# c200_rev_b.net
KiCad netlist of a schematic drawn in EAGLE
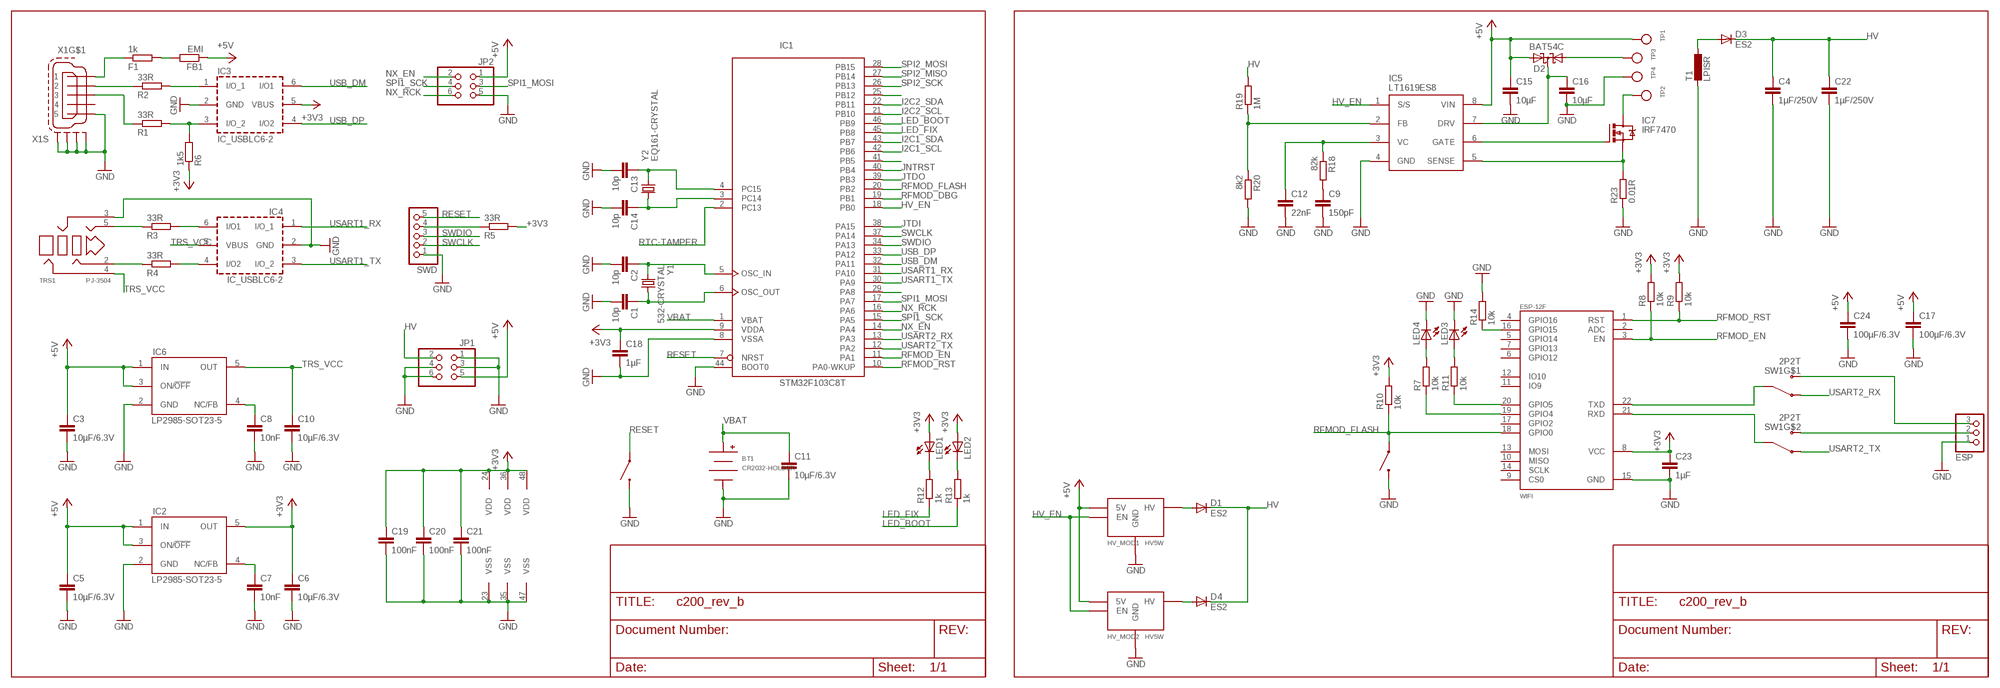
[diagram p0: schematic, sheet 1]

(export (version "E")
  (design (tool "Eeschema 10.0.6"))
  (components
    (comp (ref "BT1")
      (value "CR2032-HOLDER")
      (footprint "eagle-import:CH28-2032LF")
      (libsource (lib "eagle-import") (part "CR2032-HOLDER"))
    )
    (comp (ref "C1")
      (value "10p")
      (footprint "eagle-import:C0603")
      (libsource (lib "eagle-import") (part "C-EUC0603"))
    )
    (comp (ref "C2")
      (value "10p")
      (footprint "eagle-import:C0603")
      (libsource (lib "eagle-import") (part "C-EUC0603"))
    )
    (comp (ref "C3")
      (value "10µF/6.3V")
      (footprint "eagle-import:C0603")
      (libsource (lib "eagle-import") (part "C-EUC0603"))
    )
    (comp (ref "C4")
      (value "1µF/250V")
      (footprint "eagle-import:C2220K")
      (libsource (lib "eagle-import") (part "C-EUC2220K"))
    )
    (comp (ref "C5")
      (value "10µF/6.3V")
      (footprint "eagle-import:C0603")
      (libsource (lib "eagle-import") (part "C-EUC0603"))
    )
    (comp (ref "C6")
      (value "10µF/6.3V")
      (footprint "eagle-import:C0603")
      (libsource (lib "eagle-import") (part "C-EUC0603"))
    )
    (comp (ref "C7")
      (value "10nF")
      (footprint "eagle-import:C0603")
      (libsource (lib "eagle-import") (part "C-EUC0603"))
    )
    (comp (ref "C8")
      (value "10nF")
      (footprint "eagle-import:C0603")
      (libsource (lib "eagle-import") (part "C-EUC0603"))
    )
    (comp (ref "C9")
      (value "150pF")
      (footprint "eagle-import:C0603")
      (libsource (lib "eagle-import") (part "C-EUC0603"))
    )
    (comp (ref "C10")
      (value "10µF/6.3V")
      (footprint "eagle-import:C0603")
      (libsource (lib "eagle-import") (part "C-EUC0603"))
    )
    (comp (ref "C11")
      (value "10µF/6.3V")
      (footprint "eagle-import:C0603")
      (libsource (lib "eagle-import") (part "C-EUC0603"))
    )
    (comp (ref "C12")
      (value "22nF")
      (footprint "eagle-import:C0603")
      (libsource (lib "eagle-import") (part "C-EUC0603"))
    )
    (comp (ref "C13")
      (value "10p")
      (footprint "eagle-import:C0603")
      (libsource (lib "eagle-import") (part "C-EUC0603"))
    )
    (comp (ref "C14")
      (value "10p")
      (footprint "eagle-import:C0603")
      (libsource (lib "eagle-import") (part "C-EUC0603"))
    )
    (comp (ref "C15")
      (value "10µF")
      (footprint "eagle-import:C0603")
      (libsource (lib "eagle-import") (part "C-EUC0603"))
    )
    (comp (ref "C16")
      (value "10µF")
      (footprint "eagle-import:C0603")
      (libsource (lib "eagle-import") (part "C-EUC0603"))
    )
    (comp (ref "C17")
      (value "100µF/6.3V")
      (footprint "eagle-import:C1210")
      (libsource (lib "eagle-import") (part "C-EUC1210"))
    )
    (comp (ref "C18")
      (value "1µF")
      (footprint "eagle-import:C0603")
      (libsource (lib "eagle-import") (part "C-EUC0603"))
    )
    (comp (ref "C19")
      (value "100nF")
      (footprint "eagle-import:C0603")
      (libsource (lib "eagle-import") (part "C-EUC0603"))
    )
    (comp (ref "C20")
      (value "100nF")
      (footprint "eagle-import:C0603")
      (libsource (lib "eagle-import") (part "C-EUC0603"))
    )
    (comp (ref "C21")
      (value "100nF")
      (footprint "eagle-import:C0603")
      (libsource (lib "eagle-import") (part "C-EUC0603"))
    )
    (comp (ref "C22")
      (value "1µF/250V")
      (footprint "eagle-import:C2220K")
      (libsource (lib "eagle-import") (part "C-EUC2220K"))
    )
    (comp (ref "C23")
      (value "1µF")
      (footprint "eagle-import:C0603")
      (libsource (lib "eagle-import") (part "C-EUC0603"))
    )
    (comp (ref "C24")
      (value "100µF/6.3V")
      (footprint "eagle-import:C1210")
      (libsource (lib "eagle-import") (part "C-EUC1210"))
    )
    (comp (ref "D1")
      (value "ES2")
      (footprint "eagle-import:DO-214AA")
      (libsource (lib "eagle-import") (part "ES2"))
    )
    (comp (ref "D2")
      (value "BAT54C")
      (footprint "eagle-import:SOT23")
      (libsource (lib "eagle-import") (part "BAT54C"))
    )
    (comp (ref "D3")
      (value "ES2")
      (footprint "eagle-import:DO-214AA")
      (libsource (lib "eagle-import") (part "ES2"))
    )
    (comp (ref "D4")
      (value "ES2")
      (footprint "eagle-import:DO-214AA")
      (libsource (lib "eagle-import") (part "ES2"))
    )
    (comp (ref "ESP")
      (value "HEADER-1X3ROUND")
      (footprint "eagle-import:1X03_ROUND")
      (libsource (lib "eagle-import") (part "HEADER-1X3ROUND"))
    )
    (comp (ref "F1")
      (value "1k")
      (footprint "eagle-import:R0603")
      (libsource (lib "eagle-import") (part "R-EU_R0603"))
    )
    (comp (ref "FB1")
      (value "EMI")
      (footprint "eagle-import:R0603")
      (libsource (lib "eagle-import") (part "R-EU_R0603"))
    )
    (comp (ref "FLASH")
      (value "TACT-SWITCH-40-40")
      (footprint "eagle-import:40-40")
      (libsource (lib "eagle-import") (part "TACT-SWITCH-40-40"))
    )
    (comp (ref "HV_MOD1")
      (value "HV5W")
      (footprint "eagle-import:HV5W-D")
      (libsource (lib "eagle-import") (part "HV5W"))
    )
    (comp (ref "HV_MOD2")
      (value "HV5W")
      (footprint "eagle-import:HV5W-D")
      (libsource (lib "eagle-import") (part "HV5W"))
    )
    (comp (ref "IC1")
      (value "STM32F103C8T")
      (footprint "eagle-import:LQFP48")
      (libsource (lib "eagle-import") (part "STM32F103CT8"))
    )
    (comp (ref "IC2")
      (value "LP2985-SOT23-5")
      (footprint "eagle-import:SOT23-5")
      (libsource (lib "eagle-import") (part "LP2985-SOT23-5"))
    )
    (comp (ref "IC3")
      (value "IC_USBLC6-2")
      (footprint "eagle-import:SOT-23-6L")
      (libsource (lib "eagle-import") (part "IC_USBLC6-2"))
    )
    (comp (ref "IC4")
      (value "IC_USBLC6-2")
      (footprint "eagle-import:SOT-23-6L")
      (libsource (lib "eagle-import") (part "IC_USBLC6-2"))
    )
    (comp (ref "IC5")
      (value "LT1619ES8")
      (footprint "eagle-import:SO8")
      (libsource (lib "eagle-import") (part "LT1619ES8"))
    )
    (comp (ref "IC6")
      (value "LP2985-SOT23-5")
      (footprint "eagle-import:SOT23-5")
      (libsource (lib "eagle-import") (part "LP2985-SOT23-5"))
    )
    (comp (ref "IC7")
      (value "IRF7470")
      (footprint "eagle-import:SO8")
      (libsource (lib "eagle-import") (part "IRF7470"))
    )
    (comp (ref "ISP")
      (value "TACT-SWITCH-40-40")
      (footprint "eagle-import:40-40")
      (libsource (lib "eagle-import") (part "TACT-SWITCH-40-40"))
    )
    (comp (ref "JP1")
      (value "PINHD-2X3_2.54-SMD")
      (footprint "eagle-import:2X03SMD")
      (libsource (lib "eagle-import") (part "PINHD-2X3_2.54-SMD"))
    )
    (comp (ref "JP2")
      (value "PINHD-2X3_2.54-SMD")
      (footprint "eagle-import:2X03SMD")
      (libsource (lib "eagle-import") (part "PINHD-2X3_2.54-SMD"))
    )
    (comp (ref "LED1")
      (value "LEDCHIP-LED0603")
      (footprint "eagle-import:CHIP-LED0603")
      (libsource (lib "eagle-import") (part "LEDCHIP-LED0603"))
    )
    (comp (ref "LED2")
      (value "LEDCHIP-LED0603")
      (footprint "eagle-import:CHIP-LED0603")
      (libsource (lib "eagle-import") (part "LEDCHIP-LED0603"))
    )
    (comp (ref "LED3")
      (value "LEDCHIP-LED0603")
      (footprint "eagle-import:CHIP-LED0603")
      (libsource (lib "eagle-import") (part "LEDCHIP-LED0603"))
    )
    (comp (ref "LED4")
      (value "LEDCHIP-LED0603")
      (footprint "eagle-import:CHIP-LED0603")
      (libsource (lib "eagle-import") (part "LEDCHIP-LED0603"))
    )
    (comp (ref "R1")
      (value "33R")
      (footprint "eagle-import:R0603")
      (libsource (lib "eagle-import") (part "R-EU_R0603"))
    )
    (comp (ref "R2")
      (value "33R")
      (footprint "eagle-import:R0603")
      (libsource (lib "eagle-import") (part "R-EU_R0603"))
    )
    (comp (ref "R3")
      (value "33R")
      (footprint "eagle-import:R0603")
      (libsource (lib "eagle-import") (part "R-EU_R0603"))
    )
    (comp (ref "R4")
      (value "33R")
      (footprint "eagle-import:R0603")
      (libsource (lib "eagle-import") (part "R-EU_R0603"))
    )
    (comp (ref "R5")
      (value "33R")
      (footprint "eagle-import:R0603")
      (libsource (lib "eagle-import") (part "R-EU_R0603"))
    )
    (comp (ref "R6")
      (value "1k5")
      (footprint "eagle-import:R0603")
      (libsource (lib "eagle-import") (part "R-EU_R0603"))
    )
    (comp (ref "R7")
      (value "10k")
      (footprint "eagle-import:R0603")
      (libsource (lib "eagle-import") (part "R-EU_R0603"))
    )
    (comp (ref "R8")
      (value "10k")
      (footprint "eagle-import:R0603")
      (libsource (lib "eagle-import") (part "R-EU_R0603"))
    )
    (comp (ref "R9")
      (value "10k")
      (footprint "eagle-import:R0603")
      (libsource (lib "eagle-import") (part "R-EU_R0603"))
    )
    (comp (ref "R10")
      (value "10k")
      (footprint "eagle-import:R0603")
      (libsource (lib "eagle-import") (part "R-EU_R0603"))
    )
    (comp (ref "R11")
      (value "10k")
      (footprint "eagle-import:R0603")
      (libsource (lib "eagle-import") (part "R-EU_R0603"))
    )
    (comp (ref "R12")
      (value "1k")
      (footprint "eagle-import:R0603")
      (libsource (lib "eagle-import") (part "R-EU_R0603"))
    )
    (comp (ref "R13")
      (value "1k")
      (footprint "eagle-import:R0603")
      (libsource (lib "eagle-import") (part "R-EU_R0603"))
    )
    (comp (ref "R14")
      (value "10k")
      (footprint "eagle-import:R0603")
      (libsource (lib "eagle-import") (part "R-EU_R0603"))
    )
    (comp (ref "R18")
      (value "82k")
      (footprint "eagle-import:R0603")
      (libsource (lib "eagle-import") (part "R-EU_R0603"))
    )
    (comp (ref "R19")
      (value "1M")
      (footprint "eagle-import:M1206")
      (libsource (lib "eagle-import") (part "R-EU_M1206"))
    )
    (comp (ref "R20")
      (value "8k2")
      (footprint "eagle-import:R0603")
      (libsource (lib "eagle-import") (part "R-EU_R0603"))
    )
    (comp (ref "R23")
      (value "0.01R")
      (footprint "eagle-import:R1206")
      (libsource (lib "eagle-import") (part "R-EU_R1206"))
    )
    (comp (ref "SW1")
      (value "2P2T")
      (footprint "eagle-import:MSS22D18")
      (libsource (lib "eagle-import") (part "2P2T"))
    )
    (comp (ref "SWD")
      (value "HEADER-1X5ROUND")
      (footprint "eagle-import:1X05_ROUND")
      (libsource (lib "eagle-import") (part "HEADER-1X5ROUND"))
    )
    (comp (ref "T1")
      (value "LPISR")
      (footprint "eagle-import:PISR")
      (libsource (lib "eagle-import") (part "LPISR"))
    )
    (comp (ref "TP1")
      (value "TESTPOINTROUND2MM")
      (footprint "eagle-import:TESTPOINT_ROUND_2MM")
      (libsource (lib "eagle-import") (part "TESTPOINTROUND2MM"))
    )
    (comp (ref "TP2")
      (value "TESTPOINTROUND2MM")
      (footprint "eagle-import:TESTPOINT_ROUND_2MM")
      (libsource (lib "eagle-import") (part "TESTPOINTROUND2MM"))
    )
    (comp (ref "TP3")
      (value "TESTPOINTROUND2MM")
      (footprint "eagle-import:TESTPOINT_ROUND_2MM")
      (libsource (lib "eagle-import") (part "TESTPOINTROUND2MM"))
    )
    (comp (ref "TP4")
      (value "TESTPOINTROUND2MM")
      (footprint "eagle-import:TESTPOINT_ROUND_2MM")
      (libsource (lib "eagle-import") (part "TESTPOINTROUND2MM"))
    )
    (comp (ref "TRS1")
      (value "PJ-3504")
      (footprint "eagle-import:YD-PJ-3504")
      (libsource (lib "eagle-import") (part "PJ-3504"))
    )
    (comp (ref "WIFI")
      (value "ESP-12F")
      (footprint "eagle-import:ESP-12F")
      (libsource (lib "eagle-import") (part "ESP-12F"))
    )
    (comp (ref "X1")
      (value "MINI-USB-SCHIELD-32005-201")
      (footprint "eagle-import:32005-201")
      (libsource (lib "eagle-import") (part "MINI-USB-SCHIELD-32005-201"))
    )
    (comp (ref "Y1")
      (value "532-CRYSTAL")
      (footprint "eagle-import:2PIN50X32")
      (libsource (lib "eagle-import") (part "532-CRYSTAL"))
    )
    (comp (ref "Y2")
      (value "EQ161-CRYSTAL")
      (footprint "eagle-import:EQ161")
      (libsource (lib "eagle-import") (part "EQ161-CRYSTAL"))
    )
  )
  (nets
    (net (code "1") (name "+3V3") (class "Default")
      (node (ref "C18") (pin "1") (pinfunction "1_1") (pintype "passive"))
      (node (ref "C19") (pin "1") (pinfunction "1_1") (pintype "passive"))
      (node (ref "C20") (pin "1") (pinfunction "1_1") (pintype "passive"))
      (node (ref "C21") (pin "1") (pinfunction "1_1") (pintype "passive"))
      (node (ref "C23") (pin "1") (pinfunction "1_1") (pintype "passive"))
      (node (ref "C6") (pin "1") (pinfunction "1_1") (pintype "passive"))
      (node (ref "IC1") (pin "24") (pinfunction "VDD_24") (pintype "power_in"))
      (node (ref "IC1") (pin "36") (pinfunction "VDD_36") (pintype "power_in"))
      (node (ref "IC1") (pin "48") (pinfunction "VDD_48") (pintype "power_in"))
      (node (ref "IC1") (pin "9") (pinfunction "VDDA_9") (pintype "power_in"))
      (node (ref "IC2") (pin "5") (pinfunction "OUT_5") (pintype "bidirectional"))
      (node (ref "IC3") (pin "5") (pinfunction "VBUS_5") (pintype "bidirectional"))
      (node (ref "LED1") (pin "A") (pinfunction "A_A") (pintype "passive"))
      (node (ref "LED2") (pin "A") (pinfunction "A_A") (pintype "passive"))
      (node (ref "R10") (pin "2") (pinfunction "2_2") (pintype "passive"))
      (node (ref "R5") (pin "2") (pinfunction "2_2") (pintype "passive"))
      (node (ref "R6") (pin "1") (pinfunction "1_1") (pintype "passive"))
      (node (ref "R8") (pin "2") (pinfunction "2_2") (pintype "passive"))
      (node (ref "R9") (pin "2") (pinfunction "2_2") (pintype "passive"))
      (node (ref "WIFI") (pin "8") (pinfunction "VCC_8") (pintype "bidirectional"))
    )
    (net (code "2") (name "+5V") (class "Default")
      (node (ref "C15") (pin "1") (pinfunction "1_1") (pintype "passive"))
      (node (ref "C17") (pin "1") (pinfunction "1_1") (pintype "passive"))
      (node (ref "C24") (pin "1") (pinfunction "1_1") (pintype "passive"))
      (node (ref "C3") (pin "1") (pinfunction "1_1") (pintype "passive"))
      (node (ref "C5") (pin "1") (pinfunction "1_1") (pintype "passive"))
      (node (ref "D2") (pin "2") (pinfunction "A2_2") (pintype "passive"))
      (node (ref "FB1") (pin "1") (pinfunction "1_1") (pintype "passive"))
      (node (ref "HV_MOD1") (pin "+5V") (pinfunction "5V_+5V") (pintype "bidirectional"))
      (node (ref "HV_MOD2") (pin "+5V") (pinfunction "5V_+5V") (pintype "bidirectional"))
      (node (ref "IC2") (pin "1") (pinfunction "IN_1") (pintype "bidirectional"))
      (node (ref "IC2") (pin "3") (pinfunction "ON/~{OFF}_3") (pintype "bidirectional"))
      (node (ref "IC5") (pin "8") (pinfunction "VIN_8") (pintype "bidirectional"))
      (node (ref "IC6") (pin "1") (pinfunction "IN_1") (pintype "bidirectional"))
      (node (ref "IC6") (pin "3") (pinfunction "ON/~{OFF}_3") (pintype "bidirectional"))
      (node (ref "JP1") (pin "5") (pinfunction "5_5") (pintype "passive"))
      (node (ref "JP2") (pin "1") (pinfunction "1_1") (pintype "passive"))
      (node (ref "TP1") (pin "P$1") (pinfunction "P$1_P$1") (pintype "bidirectional"))
    )
    (net (code "3") (name "/HV") (class "Default")
      (node (ref "C22") (pin "1") (pinfunction "1_1") (pintype "passive"))
      (node (ref "C4") (pin "1") (pinfunction "1_1") (pintype "passive"))
      (node (ref "D1") (pin "C") (pinfunction "C_C") (pintype "passive"))
      (node (ref "D3") (pin "C") (pinfunction "C_C") (pintype "passive"))
      (node (ref "D4") (pin "C") (pinfunction "C_C") (pintype "passive"))
      (node (ref "JP1") (pin "2") (pinfunction "2_2") (pintype "passive"))
      (node (ref "R19") (pin "2") (pinfunction "2_2") (pintype "passive"))
    )
    (net (code "4") (name "/HV_EN") (class "Default")
      (node (ref "HV_MOD1") (pin "EN") (pinfunction "EN_EN") (pintype "bidirectional"))
      (node (ref "HV_MOD2") (pin "EN") (pinfunction "EN_EN") (pintype "bidirectional"))
      (node (ref "IC1") (pin "18") (pinfunction "PB0_18") (pintype "bidirectional"))
      (node (ref "IC5") (pin "1") (pinfunction "S/S_1") (pintype "bidirectional"))
    )
    (net (code "5") (name "/I2C1_SCL") (class "Default")
      (node (ref "IC1") (pin "42") (pinfunction "PB6_42") (pintype "bidirectional"))
    )
    (net (code "6") (name "/I2C1_SDA") (class "Default")
      (node (ref "IC1") (pin "43") (pinfunction "PB7_43") (pintype "bidirectional"))
    )
    (net (code "7") (name "/I2C2_SCL") (class "Default")
      (node (ref "IC1") (pin "21") (pinfunction "PB10_21") (pintype "bidirectional"))
    )
    (net (code "8") (name "/I2C2_SDA") (class "Default")
      (node (ref "IC1") (pin "22") (pinfunction "PB11_22") (pintype "bidirectional"))
    )
    (net (code "9") (name "/JNTRST") (class "Default")
      (node (ref "IC1") (pin "40") (pinfunction "PB4_40") (pintype "bidirectional"))
    )
    (net (code "10") (name "/JTDI") (class "Default")
      (node (ref "IC1") (pin "38") (pinfunction "PA15_38") (pintype "bidirectional"))
    )
    (net (code "11") (name "/JTDO") (class "Default")
      (node (ref "IC1") (pin "39") (pinfunction "PB3_39") (pintype "bidirectional"))
    )
    (net (code "12") (name "/LED_BOOT") (class "Default")
      (node (ref "IC1") (pin "46") (pinfunction "PB9_46") (pintype "bidirectional"))
      (node (ref "R13") (pin "1") (pinfunction "1_1") (pintype "passive"))
    )
    (net (code "13") (name "/LED_FIX") (class "Default")
      (node (ref "IC1") (pin "45") (pinfunction "PB8_45") (pintype "bidirectional"))
      (node (ref "R12") (pin "1") (pinfunction "1_1") (pintype "passive"))
    )
    (net (code "14") (name "/NX_EN") (class "Default")
      (node (ref "IC1") (pin "14") (pinfunction "PA4_14") (pintype "bidirectional"))
      (node (ref "JP2") (pin "2") (pinfunction "2_2") (pintype "passive"))
    )
    (net (code "15") (name "/NX_RCK") (class "Default")
      (node (ref "IC1") (pin "16") (pinfunction "PA6_16") (pintype "bidirectional"))
      (node (ref "JP2") (pin "6") (pinfunction "6_6") (pintype "passive"))
    )
    (net (code "16") (name "/RESET") (class "Default")
      (node (ref "IC1") (pin "7") (pinfunction "NRST_7") (pintype "bidirectional"))
      (node (ref "ISP") (pin "3") (pinfunction "P$2_3") (pintype "bidirectional"))
      (node (ref "ISP") (pin "4") (pinfunction "P$2_4") (pintype "bidirectional"))
      (node (ref "SWD") (pin "5") (pinfunction "5_5") (pintype "passive"))
    )
    (net (code "17") (name "/RFMOD_DBG") (class "Default")
      (node (ref "IC1") (pin "19") (pinfunction "PB1_19") (pintype "bidirectional"))
    )
    (net (code "18") (name "/RFMOD_EN") (class "Default")
      (node (ref "IC1") (pin "11") (pinfunction "PA1_11") (pintype "bidirectional"))
      (node (ref "R8") (pin "1") (pinfunction "1_1") (pintype "passive"))
      (node (ref "WIFI") (pin "3") (pinfunction "EN_3") (pintype "bidirectional"))
    )
    (net (code "19") (name "/RFMOD_FLASH") (class "Default")
      (node (ref "FLASH") (pin "3") (pinfunction "P$2_3") (pintype "bidirectional"))
      (node (ref "FLASH") (pin "4") (pinfunction "P$2_4") (pintype "bidirectional"))
      (node (ref "IC1") (pin "20") (pinfunction "PB2_20") (pintype "bidirectional"))
      (node (ref "R10") (pin "1") (pinfunction "1_1") (pintype "passive"))
      (node (ref "WIFI") (pin "18") (pinfunction "GPIO0_18") (pintype "bidirectional"))
    )
    (net (code "20") (name "/RFMOD_RST") (class "Default")
      (node (ref "IC1") (pin "10") (pinfunction "PA0-WKUP_10") (pintype "bidirectional"))
      (node (ref "R9") (pin "1") (pinfunction "1_1") (pintype "passive"))
      (node (ref "WIFI") (pin "1") (pinfunction "RST_1") (pintype "bidirectional"))
    )
    (net (code "21") (name "/RTC-TAMPER") (class "Default")
      (node (ref "IC1") (pin "2") (pinfunction "PC13_2") (pintype "bidirectional"))
    )
    (net (code "22") (name "/SPI1_MOSI") (class "Default")
      (node (ref "IC1") (pin "17") (pinfunction "PA7_17") (pintype "bidirectional"))
      (node (ref "JP2") (pin "3") (pinfunction "3_3") (pintype "passive"))
    )
    (net (code "23") (name "/SPI1_SCK") (class "Default")
      (node (ref "IC1") (pin "15") (pinfunction "PA5_15") (pintype "bidirectional"))
      (node (ref "JP2") (pin "4") (pinfunction "4_4") (pintype "passive"))
    )
    (net (code "24") (name "/SPI2_MISO") (class "Default")
      (node (ref "IC1") (pin "27") (pinfunction "PB14_27") (pintype "bidirectional"))
    )
    (net (code "25") (name "/SPI2_MOSI") (class "Default")
      (node (ref "IC1") (pin "28") (pinfunction "PB15_28") (pintype "bidirectional"))
    )
    (net (code "26") (name "/SPI2_SCK") (class "Default")
      (node (ref "IC1") (pin "26") (pinfunction "PB13_26") (pintype "bidirectional"))
    )
    (net (code "27") (name "/SWCLK") (class "Default")
      (node (ref "IC1") (pin "37") (pinfunction "PA14_37") (pintype "bidirectional"))
      (node (ref "SWD") (pin "2") (pinfunction "2_2") (pintype "passive"))
    )
    (net (code "28") (name "/SWDIO") (class "Default")
      (node (ref "IC1") (pin "34") (pinfunction "PA13_34") (pintype "bidirectional"))
      (node (ref "SWD") (pin "3") (pinfunction "3_3") (pintype "passive"))
    )
    (net (code "29") (name "/TRS_VCC") (class "Default")
      (node (ref "C10") (pin "1") (pinfunction "1_1") (pintype "passive"))
      (node (ref "IC4") (pin "5") (pinfunction "VBUS_5") (pintype "bidirectional"))
      (node (ref "IC6") (pin "5") (pinfunction "OUT_5") (pintype "bidirectional"))
      (node (ref "TRS1") (pin "4") (pinfunction "4_4") (pintype "bidirectional"))
    )
    (net (code "30") (name "/USART1_RX") (class "Default")
      (node (ref "IC1") (pin "31") (pinfunction "PA10_31") (pintype "bidirectional"))
      (node (ref "IC4") (pin "1") (pinfunction "I/O_1_1") (pintype "bidirectional"))
    )
    (net (code "31") (name "/USART1_TX") (class "Default")
      (node (ref "IC1") (pin "30") (pinfunction "PA9_30") (pintype "bidirectional"))
      (node (ref "IC4") (pin "3") (pinfunction "I/O_2_3") (pintype "bidirectional"))
    )
    (net (code "32") (name "/USART2_RX") (class "Default")
      (node (ref "IC1") (pin "13") (pinfunction "PA3_13") (pintype "bidirectional"))
      (node (ref "SW1") (pin "A1") (pinfunction "A_A1") (pintype "bidirectional"))
    )
    (net (code "33") (name "/USART2_TX") (class "Default")
      (node (ref "IC1") (pin "12") (pinfunction "PA2_12") (pintype "bidirectional"))
      (node (ref "SW1") (pin "A2") (pinfunction "A_A2") (pintype "bidirectional"))
    )
    (net (code "34") (name "/USB_DM") (class "Default")
      (node (ref "IC1") (pin "32") (pinfunction "PA11_32") (pintype "bidirectional"))
      (node (ref "IC3") (pin "6") (pinfunction "I/O1_6") (pintype "bidirectional"))
    )
    (net (code "35") (name "/USB_DP") (class "Default")
      (node (ref "IC1") (pin "33") (pinfunction "PA12_33") (pintype "bidirectional"))
      (node (ref "IC3") (pin "4") (pinfunction "I/O2_4") (pintype "bidirectional"))
    )
    (net (code "36") (name "/VBAT") (class "Default")
      (node (ref "BT1") (pin "POS") (pinfunction "POS_POS") (pintype "bidirectional"))
      (node (ref "C11") (pin "1") (pinfunction "1_1") (pintype "passive"))
      (node (ref "IC1") (pin "1") (pinfunction "VBAT_1") (pintype "power_in"))
    )
    (net (code "37") (name "GND") (class "Default")
      (node (ref "BT1") (pin "NEG") (pinfunction "NEG_NEG") (pintype "bidirectional"))
      (node (ref "C1") (pin "2") (pinfunction "2_2") (pintype "passive"))
      (node (ref "C10") (pin "2") (pinfunction "2_2") (pintype "passive"))
      (node (ref "C11") (pin "2") (pinfunction "2_2") (pintype "passive"))
      (node (ref "C12") (pin "2") (pinfunction "2_2") (pintype "passive"))
      (node (ref "C13") (pin "2") (pinfunction "2_2") (pintype "passive"))
      (node (ref "C14") (pin "2") (pinfunction "2_2") (pintype "passive"))
      (node (ref "C15") (pin "2") (pinfunction "2_2") (pintype "passive"))
      (node (ref "C16") (pin "2") (pinfunction "2_2") (pintype "passive"))
      (node (ref "C17") (pin "2") (pinfunction "2_2") (pintype "passive"))
      (node (ref "C18") (pin "2") (pinfunction "2_2") (pintype "passive"))
      (node (ref "C19") (pin "2") (pinfunction "2_2") (pintype "passive"))
      (node (ref "C2") (pin "2") (pinfunction "2_2") (pintype "passive"))
      (node (ref "C20") (pin "2") (pinfunction "2_2") (pintype "passive"))
      (node (ref "C21") (pin "2") (pinfunction "2_2") (pintype "passive"))
      (node (ref "C22") (pin "2") (pinfunction "2_2") (pintype "passive"))
      (node (ref "C23") (pin "2") (pinfunction "2_2") (pintype "passive"))
      (node (ref "C24") (pin "2") (pinfunction "2_2") (pintype "passive"))
      (node (ref "C3") (pin "2") (pinfunction "2_2") (pintype "passive"))
      (node (ref "C4") (pin "2") (pinfunction "2_2") (pintype "passive"))
      (node (ref "C5") (pin "2") (pinfunction "2_2") (pintype "passive"))
      (node (ref "C6") (pin "2") (pinfunction "2_2") (pintype "passive"))
      (node (ref "C7") (pin "2") (pinfunction "2_2") (pintype "passive"))
      (node (ref "C8") (pin "2") (pinfunction "2_2") (pintype "passive"))
      (node (ref "C9") (pin "2") (pinfunction "2_2") (pintype "passive"))
      (node (ref "ESP") (pin "1") (pinfunction "1_1") (pintype "passive"))
      (node (ref "FLASH") (pin "1") (pinfunction "P$1_1") (pintype "bidirectional"))
      (node (ref "FLASH") (pin "2") (pinfunction "P$1_2") (pintype "bidirectional"))
      (node (ref "HV_MOD1") (pin "GND1") (pinfunction "GND_GND1") (pintype "bidirectional"))
      (node (ref "HV_MOD1") (pin "GND2") (pinfunction "GND_GND2") (pintype "bidirectional"))
      (node (ref "HV_MOD1") (pin "GND3") (pinfunction "GND_GND3") (pintype "bidirectional"))
      (node (ref "HV_MOD2") (pin "GND1") (pinfunction "GND_GND1") (pintype "bidirectional"))
      (node (ref "HV_MOD2") (pin "GND2") (pinfunction "GND_GND2") (pintype "bidirectional"))
      (node (ref "HV_MOD2") (pin "GND3") (pinfunction "GND_GND3") (pintype "bidirectional"))
      (node (ref "IC1") (pin "23") (pinfunction "VSS_23") (pintype "power_in"))
      (node (ref "IC1") (pin "35") (pinfunction "VSS_35") (pintype "power_in"))
      (node (ref "IC1") (pin "44") (pinfunction "BOOT0_44") (pintype "input"))
      (node (ref "IC1") (pin "47") (pinfunction "VSS_47") (pintype "power_in"))
      (node (ref "IC1") (pin "8") (pinfunction "VSSA_8") (pintype "power_in"))
      (node (ref "IC2") (pin "2") (pinfunction "GND_2") (pintype "bidirectional"))
      (node (ref "IC3") (pin "2") (pinfunction "GND_2") (pintype "bidirectional"))
      (node (ref "IC4") (pin "2") (pinfunction "GND_2") (pintype "bidirectional"))
      (node (ref "IC5") (pin "4") (pinfunction "GND_4") (pintype "bidirectional"))
      (node (ref "IC6") (pin "2") (pinfunction "GND_2") (pintype "bidirectional"))
      (node (ref "ISP") (pin "1") (pinfunction "P$1_1") (pintype "bidirectional"))
      (node (ref "ISP") (pin "2") (pinfunction "P$1_2") (pintype "bidirectional"))
      (node (ref "JP1") (pin "1") (pinfunction "1_1") (pintype "passive"))
      (node (ref "JP1") (pin "3") (pinfunction "3_3") (pintype "passive"))
      (node (ref "JP1") (pin "4") (pinfunction "4_4") (pintype "passive"))
      (node (ref "JP1") (pin "6") (pinfunction "6_6") (pintype "passive"))
      (node (ref "JP2") (pin "5") (pinfunction "5_5") (pintype "passive"))
      (node (ref "LED3") (pin "C") (pinfunction "C_C") (pintype "passive"))
      (node (ref "LED4") (pin "C") (pinfunction "C_C") (pintype "passive"))
      (node (ref "R14") (pin "2") (pinfunction "2_2") (pintype "passive"))
      (node (ref "R20") (pin "2") (pinfunction "2_2") (pintype "passive"))
      (node (ref "R23") (pin "1") (pinfunction "1_1") (pintype "passive"))
      (node (ref "SWD") (pin "1") (pinfunction "1_1") (pintype "passive"))
      (node (ref "T1") (pin "P$2") (pinfunction "2_P$2") (pintype "passive"))
      (node (ref "TP4") (pin "P$1") (pinfunction "P$1_P$1") (pintype "bidirectional"))
      (node (ref "TRS1") (pin "3") (pinfunction "3_3") (pintype "bidirectional"))
      (node (ref "WIFI") (pin "15") (pinfunction "GND_15") (pintype "bidirectional"))
      (node (ref "X1") (pin "5") (pinfunction "5_5") (pintype "passive"))
      (node (ref "X1") (pin "M1") (pinfunction "S1_M1") (pintype "passive"))
      (node (ref "X1") (pin "M2") (pinfunction "S2_M2") (pintype "passive"))
      (node (ref "X1") (pin "M3") (pinfunction "S3_M3") (pintype "passive"))
      (node (ref "X1") (pin "M4") (pinfunction "S4_M4") (pintype "passive"))
    )
    (net (code "38") (name "Net-(C9-Pad1)") (class "Default")
      (node (ref "C9") (pin "1") (pinfunction "1_1") (pintype "passive"))
      (node (ref "R18") (pin "2") (pinfunction "2_2") (pintype "passive"))
    )
    (net (code "39") (name "Net-(D1-PadA)") (class "Default")
      (node (ref "D1") (pin "A") (pinfunction "A_A") (pintype "passive"))
      (node (ref "HV_MOD1") (pin "HV") (pinfunction "HV_HV") (pintype "bidirectional"))
    )
    (net (code "40") (name "Net-(D2-A1)") (class "Default")
      (node (ref "D2") (pin "1") (pinfunction "A1_1") (pintype "passive"))
      (node (ref "TP3") (pin "P$1") (pinfunction "P$1_P$1") (pintype "bidirectional"))
    )
    (net (code "41") (name "Net-(D2-CC)") (class "Default")
      (node (ref "C16") (pin "1") (pinfunction "1_1") (pintype "passive"))
      (node (ref "D2") (pin "3") (pinfunction "CC_3") (pintype "passive"))
      (node (ref "IC5") (pin "7") (pinfunction "DRV_7") (pintype "bidirectional"))
    )
    (net (code "42") (name "Net-(D4-PadA)") (class "Default")
      (node (ref "D4") (pin "A") (pinfunction "A_A") (pintype "passive"))
      (node (ref "HV_MOD2") (pin "HV") (pinfunction "HV_HV") (pintype "bidirectional"))
    )
    (net (code "43") (name "Net-(F1-Pad1)") (class "Default")
      (node (ref "F1") (pin "1") (pinfunction "1_1") (pintype "passive"))
      (node (ref "X1") (pin "1") (pinfunction "1_1") (pintype "passive"))
    )
    (net (code "44") (name "Net-(F1-Pad2)") (class "Default")
      (node (ref "F1") (pin "2") (pinfunction "2_2") (pintype "passive"))
      (node (ref "FB1") (pin "2") (pinfunction "2_2") (pintype "passive"))
    )
    (net (code "45") (name "Net-(IC1A-OSC_IN)") (class "Default")
      (node (ref "C2") (pin "1") (pinfunction "1_1") (pintype "passive"))
      (node (ref "IC1") (pin "5") (pinfunction "OSC_IN_5") (pintype "bidirectional"))
      (node (ref "Y1") (pin "P$2") (pinfunction "2_P$2") (pintype "passive"))
    )
    (net (code "46") (name "Net-(IC1A-OSC_OUT)") (class "Default")
      (node (ref "C1") (pin "1") (pinfunction "1_1") (pintype "passive"))
      (node (ref "IC1") (pin "6") (pinfunction "OSC_OUT_6") (pintype "bidirectional"))
      (node (ref "Y1") (pin "P$1") (pinfunction "1_P$1") (pintype "passive"))
    )
    (net (code "47") (name "Net-(IC1A-PC14)") (class "Default")
      (node (ref "C14") (pin "1") (pinfunction "1_1") (pintype "passive"))
      (node (ref "IC1") (pin "3") (pinfunction "PC14_3") (pintype "bidirectional"))
      (node (ref "Y2") (pin "P$2") (pinfunction "2_P$2") (pintype "passive"))
    )
    (net (code "48") (name "Net-(IC1A-PC15)") (class "Default")
      (node (ref "C13") (pin "1") (pinfunction "1_1") (pintype "passive"))
      (node (ref "IC1") (pin "4") (pinfunction "PC15_4") (pintype "bidirectional"))
      (node (ref "Y2") (pin "P$1") (pinfunction "1_P$1") (pintype "passive"))
    )
    (net (code "49") (name "Net-(IC2-NC{slash}FB)") (class "Default")
      (node (ref "C7") (pin "1") (pinfunction "1_1") (pintype "passive"))
      (node (ref "IC2") (pin "4") (pinfunction "NC/FB_4") (pintype "bidirectional"))
    )
    (net (code "50") (name "Net-(IC3-I{slash}O_1)") (class "Default")
      (node (ref "IC3") (pin "1") (pinfunction "I/O_1_1") (pintype "bidirectional"))
      (node (ref "R2") (pin "2") (pinfunction "2_2") (pintype "passive"))
    )
    (net (code "51") (name "Net-(IC3-I{slash}O_2)") (class "Default")
      (node (ref "IC3") (pin "3") (pinfunction "I/O_2_3") (pintype "bidirectional"))
      (node (ref "R1") (pin "2") (pinfunction "2_2") (pintype "passive"))
      (node (ref "R6") (pin "2") (pinfunction "2_2") (pintype "passive"))
    )
    (net (code "52") (name "Net-(IC4-I{slash}O1)") (class "Default")
      (node (ref "IC4") (pin "6") (pinfunction "I/O1_6") (pintype "bidirectional"))
      (node (ref "R3") (pin "2") (pinfunction "2_2") (pintype "passive"))
    )
    (net (code "53") (name "Net-(IC4-I{slash}O2)") (class "Default")
      (node (ref "IC4") (pin "4") (pinfunction "I/O2_4") (pintype "bidirectional"))
      (node (ref "R4") (pin "2") (pinfunction "2_2") (pintype "passive"))
    )
    (net (code "54") (name "Net-(IC5-FB)") (class "Default")
      (node (ref "IC5") (pin "2") (pinfunction "FB_2") (pintype "bidirectional"))
      (node (ref "R19") (pin "1") (pinfunction "1_1") (pintype "passive"))
      (node (ref "R20") (pin "1") (pinfunction "1_1") (pintype "passive"))
    )
    (net (code "55") (name "Net-(IC5-GATE)") (class "Default")
      (node (ref "IC5") (pin "6") (pinfunction "GATE_6") (pintype "bidirectional"))
      (node (ref "IC7") (pin "4") (pinfunction "G_4") (pintype "passive"))
    )
    (net (code "56") (name "Net-(IC5-SENSE)") (class "Default")
      (node (ref "IC5") (pin "5") (pinfunction "SENSE_5") (pintype "bidirectional"))
      (node (ref "IC7") (pin "1") (pinfunction "S_1") (pintype "passive"))
      (node (ref "IC7") (pin "2") (pinfunction "S_2") (pintype "passive"))
      (node (ref "IC7") (pin "3") (pinfunction "S_3") (pintype "passive"))
      (node (ref "R23") (pin "2") (pinfunction "2_2") (pintype "passive"))
    )
    (net (code "57") (name "Net-(IC5-VC)") (class "Default")
      (node (ref "C12") (pin "1") (pinfunction "1_1") (pintype "passive"))
      (node (ref "IC5") (pin "3") (pinfunction "VC_3") (pintype "bidirectional"))
      (node (ref "R18") (pin "1") (pinfunction "1_1") (pintype "passive"))
    )
    (net (code "58") (name "Net-(IC6-NC{slash}FB)") (class "Default")
      (node (ref "C8") (pin "1") (pinfunction "1_1") (pintype "passive"))
      (node (ref "IC6") (pin "4") (pinfunction "NC/FB_4") (pintype "bidirectional"))
    )
    (net (code "59") (name "Net-(IC7-D-Pad5)") (class "Default")
      (node (ref "IC7") (pin "5") (pinfunction "D_5") (pintype "passive"))
      (node (ref "IC7") (pin "6") (pinfunction "D_6") (pintype "passive"))
      (node (ref "IC7") (pin "7") (pinfunction "D_7") (pintype "passive"))
      (node (ref "IC7") (pin "8") (pinfunction "D_8") (pintype "passive"))
      (node (ref "TP2") (pin "P$1") (pinfunction "P$1_P$1") (pintype "bidirectional"))
    )
    (net (code "60") (name "Net-(LED1-PadC)") (class "Default")
      (node (ref "LED1") (pin "C") (pinfunction "C_C") (pintype "passive"))
      (node (ref "R12") (pin "2") (pinfunction "2_2") (pintype "passive"))
    )
    (net (code "61") (name "Net-(LED2-PadC)") (class "Default")
      (node (ref "LED2") (pin "C") (pinfunction "C_C") (pintype "passive"))
      (node (ref "R13") (pin "2") (pinfunction "2_2") (pintype "passive"))
    )
    (net (code "62") (name "Net-(LED3-PadA)") (class "Default")
      (node (ref "LED3") (pin "A") (pinfunction "A_A") (pintype "passive"))
      (node (ref "R11") (pin "2") (pinfunction "2_2") (pintype "passive"))
    )
    (net (code "63") (name "Net-(LED4-PadA)") (class "Default")
      (node (ref "LED4") (pin "A") (pinfunction "A_A") (pintype "passive"))
      (node (ref "R7") (pin "2") (pinfunction "2_2") (pintype "passive"))
    )
    (net (code "64") (name "Net-(R1-Pad1)") (class "Default")
      (node (ref "R1") (pin "1") (pinfunction "1_1") (pintype "passive"))
      (node (ref "X1") (pin "3") (pinfunction "3_3") (pintype "passive"))
    )
    (net (code "65") (name "Net-(R2-Pad1)") (class "Default")
      (node (ref "R2") (pin "1") (pinfunction "1_1") (pintype "passive"))
      (node (ref "X1") (pin "2") (pinfunction "2_2") (pintype "passive"))
    )
    (net (code "66") (name "Net-(R3-Pad1)") (class "Default")
      (node (ref "R3") (pin "1") (pinfunction "1_1") (pintype "passive"))
      (node (ref "TRS1") (pin "5") (pinfunction "5_5") (pintype "bidirectional"))
    )
    (net (code "67") (name "Net-(R4-Pad1)") (class "Default")
      (node (ref "R4") (pin "1") (pinfunction "1_1") (pintype "passive"))
      (node (ref "TRS1") (pin "2") (pinfunction "2_2") (pintype "bidirectional"))
    )
    (net (code "68") (name "Net-(R5-Pad1)") (class "Default")
      (node (ref "R5") (pin "1") (pinfunction "1_1") (pintype "passive"))
      (node (ref "SWD") (pin "4") (pinfunction "4_4") (pintype "passive"))
    )
    (net (code "69") (name "Net-(SW1A-B)") (class "Default")
      (node (ref "ESP") (pin "3") (pinfunction "3_3") (pintype "passive"))
      (node (ref "SW1") (pin "B1") (pinfunction "B_B1") (pintype "bidirectional"))
    )
    (net (code "70") (name "Net-(SW1A-C)") (class "Default")
      (node (ref "SW1") (pin "C1") (pinfunction "C_C1") (pintype "bidirectional"))
      (node (ref "WIFI") (pin "22") (pinfunction "TXD_22") (pintype "bidirectional"))
    )
    (net (code "71") (name "Net-(SW1B-B)") (class "Default")
      (node (ref "ESP") (pin "2") (pinfunction "2_2") (pintype "passive"))
      (node (ref "SW1") (pin "B2") (pinfunction "B_B2") (pintype "bidirectional"))
    )
    (net (code "72") (name "Net-(SW1B-C)") (class "Default")
      (node (ref "SW1") (pin "C2") (pinfunction "C_C2") (pintype "bidirectional"))
      (node (ref "WIFI") (pin "21") (pinfunction "RXD_21") (pintype "bidirectional"))
    )
    (net (code "73") (name "Net-(T1-1)") (class "Default")
      (node (ref "D3") (pin "A") (pinfunction "A_A") (pintype "passive"))
      (node (ref "T1") (pin "P$1") (pinfunction "1_P$1") (pintype "passive"))
    )
    (net (code "74") (name "Net-(WIFI-GPIO4)") (class "Default")
      (node (ref "R7") (pin "1") (pinfunction "1_1") (pintype "passive"))
      (node (ref "WIFI") (pin "19") (pinfunction "GPIO4_19") (pintype "bidirectional"))
    )
    (net (code "75") (name "Net-(WIFI-GPIO5)") (class "Default")
      (node (ref "R11") (pin "1") (pinfunction "1_1") (pintype "passive"))
      (node (ref "WIFI") (pin "20") (pinfunction "GPIO5_20") (pintype "bidirectional"))
    )
    (net (code "76") (name "Net-(WIFI-GPIO15)") (class "Default")
      (node (ref "R14") (pin "1") (pinfunction "1_1") (pintype "passive"))
      (node (ref "WIFI") (pin "16") (pinfunction "GPIO15_16") (pintype "bidirectional"))
    )
    (net (code "77") (name "unconnected-(IC1A-PA8-Pad29)") (class "Default")
      (node (ref "IC1") (pin "29") (pinfunction "PA8_29") (pintype "bidirectional"))
    )
    (net (code "78") (name "unconnected-(IC1A-PB5-Pad41)") (class "Default")
      (node (ref "IC1") (pin "41") (pinfunction "PB5_41") (pintype "bidirectional"))
    )
    (net (code "79") (name "unconnected-(IC1A-PB12-Pad25)") (class "Default")
      (node (ref "IC1") (pin "25") (pinfunction "PB12_25") (pintype "bidirectional"))
    )
    (net (code "80") (name "unconnected-(WIFI-ADC-Pad2)") (class "Default")
      (node (ref "WIFI") (pin "2") (pinfunction "ADC_2") (pintype "bidirectional"))
    )
    (net (code "81") (name "unconnected-(WIFI-CS0-Pad9)") (class "Default")
      (node (ref "WIFI") (pin "9") (pinfunction "CS0_9") (pintype "bidirectional"))
    )
    (net (code "82") (name "unconnected-(WIFI-GPIO2-Pad17)") (class "Default")
      (node (ref "WIFI") (pin "17") (pinfunction "GPIO2_17") (pintype "bidirectional"))
    )
    (net (code "83") (name "unconnected-(WIFI-GPIO12-Pad6)") (class "Default")
      (node (ref "WIFI") (pin "6") (pinfunction "GPIO12_6") (pintype "bidirectional"))
    )
    (net (code "84") (name "unconnected-(WIFI-GPIO13-Pad7)") (class "Default")
      (node (ref "WIFI") (pin "7") (pinfunction "GPIO13_7") (pintype "bidirectional"))
    )
    (net (code "85") (name "unconnected-(WIFI-GPIO14-Pad5)") (class "Default")
      (node (ref "WIFI") (pin "5") (pinfunction "GPIO14_5") (pintype "bidirectional"))
    )
    (net (code "86") (name "unconnected-(WIFI-GPIO16-Pad4)") (class "Default")
      (node (ref "WIFI") (pin "4") (pinfunction "GPIO16_4") (pintype "bidirectional"))
    )
    (net (code "87") (name "unconnected-(WIFI-IO9-Pad11)") (class "Default")
      (node (ref "WIFI") (pin "11") (pinfunction "IO9_11") (pintype "bidirectional"))
    )
    (net (code "88") (name "unconnected-(WIFI-IO10-Pad12)") (class "Default")
      (node (ref "WIFI") (pin "12") (pinfunction "IO10_12") (pintype "bidirectional"))
    )
    (net (code "89") (name "unconnected-(WIFI-MISO-Pad10)") (class "Default")
      (node (ref "WIFI") (pin "10") (pinfunction "MISO_10") (pintype "bidirectional"))
    )
    (net (code "90") (name "unconnected-(WIFI-MOSI-Pad13)") (class "Default")
      (node (ref "WIFI") (pin "13") (pinfunction "MOSI_13") (pintype "bidirectional"))
    )
    (net (code "91") (name "unconnected-(WIFI-SCLK-Pad14)") (class "Default")
      (node (ref "WIFI") (pin "14") (pinfunction "SCLK_14") (pintype "bidirectional"))
    )
    (net (code "92") (name "unconnected-(X1-Pad4)") (class "Default")
      (node (ref "X1") (pin "4") (pinfunction "4_4") (pintype "passive"))
    )
  )
)
